# myRolloCtl.net
KiCad netlist of a schematic drawn in EAGLE
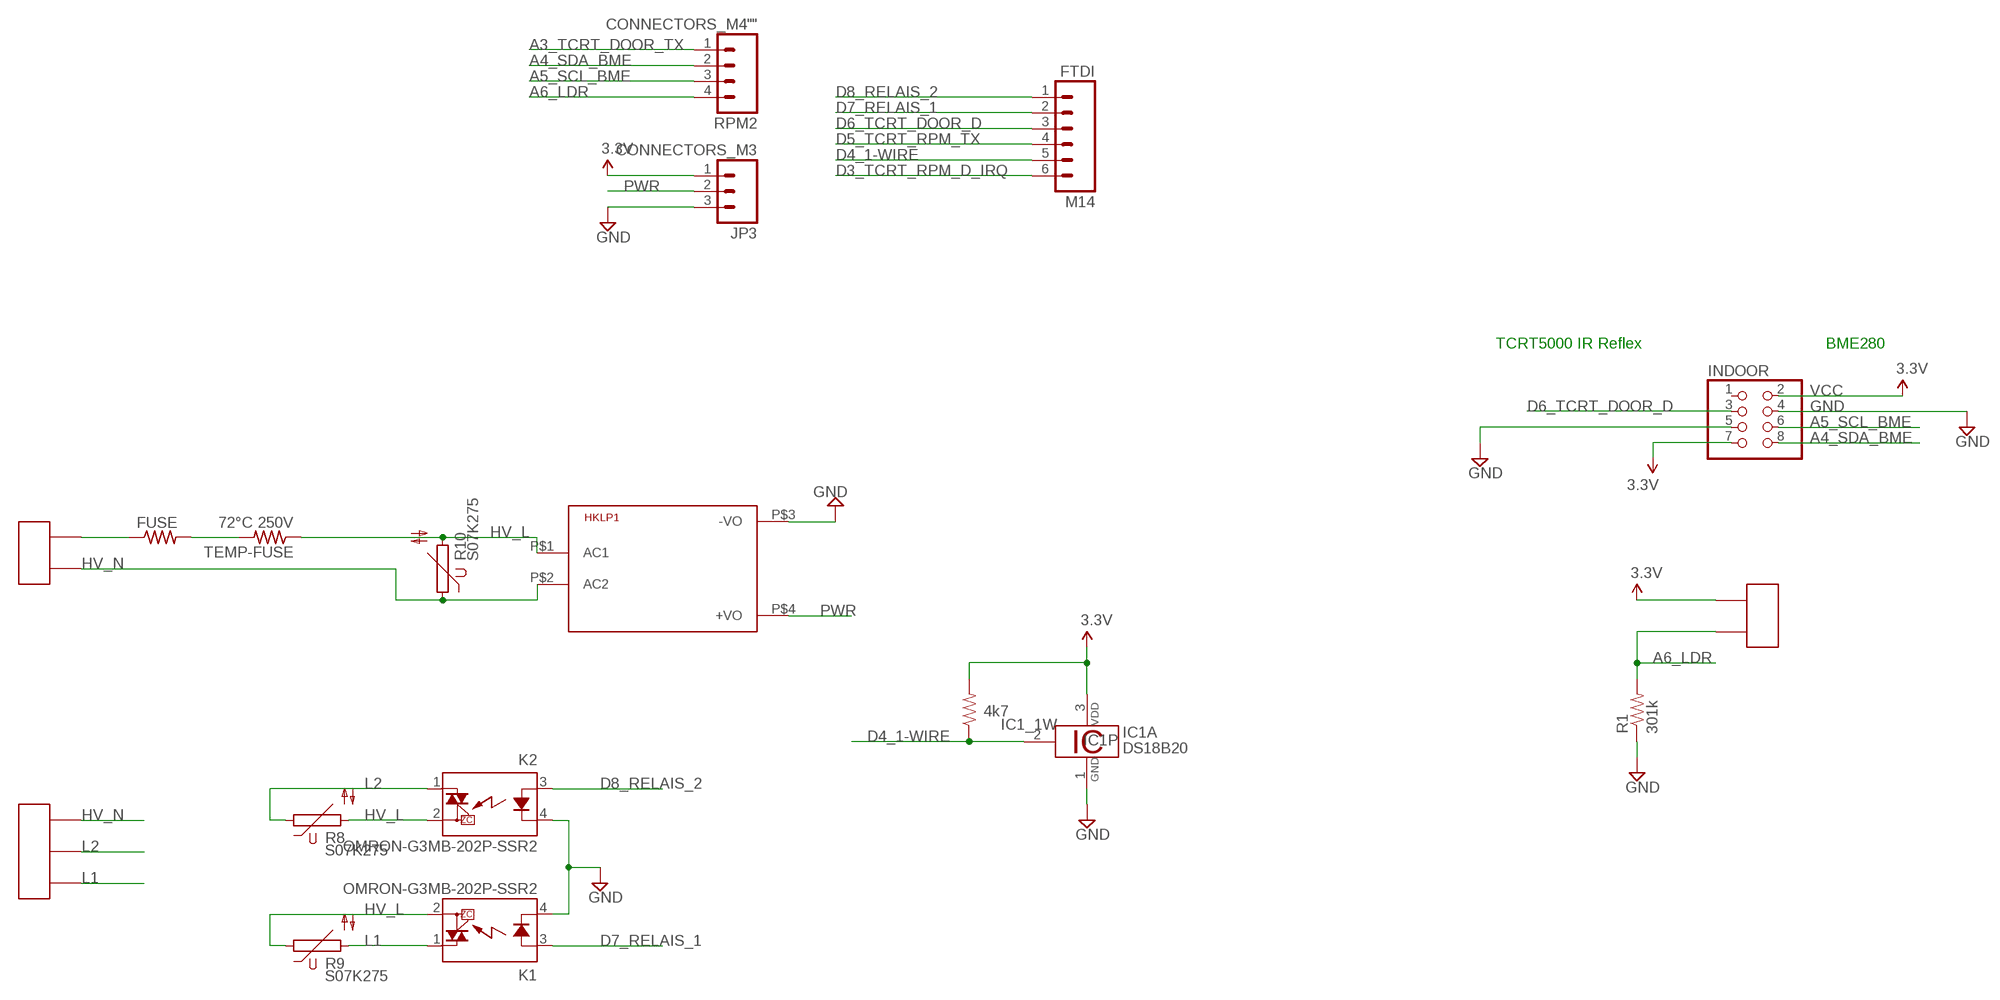
[diagram p0: schematic, sheet 1]

(export (version "E")
  (design (tool "Eeschema 10.0.6"))
  (components
    (comp (ref "FUSE")
      (value "R-US_0613/5V")
      (footprint "eagle-import:P0613V")
      (libsource (lib "eagle-import") (part "R-US_0613/5V"))
    )
    (comp (ref "HKLP1")
      (value "HKLPM01")
      (footprint "eagle-import:HKLPM01")
      (libsource (lib "eagle-import") (part "HKLPM01"))
    )
    (comp (ref "IC1")
      (value "DS18B20")
      (footprint "eagle-import:TO92-")
      (libsource (lib "eagle-import") (part "DS18B20"))
    )
    (comp (ref "INDOOR")
      (value "PINHD-2X4")
      (footprint "eagle-import:2X04")
      (libsource (lib "eagle-import") (part "PINHD-2X4"))
    )
    (comp (ref "JP3")
      (value "CONNECTORS_M3")
      (footprint "eagle-import:CONNECTORS_1X3")
      (libsource (lib "eagle-import") (part "CONNECTORS_M3"))
    )
    (comp (ref "K1")
      (value "OMRON-G3MB-202P-SSR2")
      (footprint "eagle-import:OMRON-G3MB-202P-SSR")
      (fields (field (name "MPN") "S202S02F"))
      (libsource (lib "eagle-import") (part "OMRON-G3MB-202P-SSR2"))
    )
    (comp (ref "K2")
      (value "OMRON-G3MB-202P-SSR2")
      (footprint "eagle-import:OMRON-G3MB-202P-SSR")
      (fields (field (name "MPN") "S202S02F"))
      (libsource (lib "eagle-import") (part "OMRON-G3MB-202P-SSR2"))
    )
    (comp (ref "M14")
      (value "FTDI")
      (footprint "eagle-import:1X06")
      (libsource (lib "eagle-import") (part "M06SIP"))
    )
    (comp (ref "R1")
      (value "301k")
      (footprint "eagle-import:0603-RES")
      (libsource (lib "eagle-import") (part "RESISTOR0603-RES"))
    )
    (comp (ref "R4")
      (value "4k7")
      (footprint "eagle-import:0603-RES")
      (libsource (lib "eagle-import") (part "RESISTOR0603-RES"))
    )
    (comp (ref "R8")
      (value "S07K275")
      (footprint "eagle-import:S07K275")
      (libsource (lib "eagle-import") (part "S07K275"))
    )
    (comp (ref "R9")
      (value "S07K275")
      (footprint "eagle-import:S07K275")
      (libsource (lib "eagle-import") (part "S07K275"))
    )
    (comp (ref "R10")
      (value "S07K275")
      (footprint "eagle-import:S07K275")
      (libsource (lib "eagle-import") (part "S07K275"))
    )
    (comp (ref "RPM2")
      (value "CONNECTORS_M4\"\"")
      (footprint "eagle-import:CONNECTORS_1X4")
      (libsource (lib "eagle-import") (part "CONNECTORS_M4{dblquote}{dblquote}"))
    )
    (comp (ref "TEMP-FUSE")
      (value "72°C 250V")
      (footprint "eagle-import:0207_2V")
      (libsource (lib "eagle-import") (part "R-US_0207/2V"))
    )
    (comp (ref "U$2")
      (value "HDR_2PIN")
      (footprint "eagle-import:1X02_NS")
      (libsource (lib "eagle-import") (part "HDR_2PIN"))
    )
    (comp (ref "U$3")
      (value "HDR_3PIN")
      (footprint "eagle-import:1X03_LUMBERG-KRMC_3,5MM")
      (libsource (lib "eagle-import") (part "HDR_3PIN"))
    )
    (comp (ref "U$6")
      (value "HDR_2PIN1X02_3.5MM")
      (footprint "eagle-import:1X02_LUMBERG-KRMC_3,5MM")
      (libsource (lib "eagle-import") (part "HDR_2PIN1X02_3.5MM"))
    )
  )
  (nets
    (net (code "1") (name "/A3_TCRT_DOOR_TX") (class "Default")
      (node (ref "RPM2") (pin "1") (pinfunction "1_1") (pintype "passive"))
    )
    (net (code "2") (name "/A4_SDA_BME") (class "Default")
      (node (ref "INDOOR") (pin "8") (pinfunction "8_8") (pintype "passive"))
      (node (ref "RPM2") (pin "2") (pinfunction "2_2") (pintype "passive"))
    )
    (net (code "3") (name "/A5_SCL_BME") (class "Default")
      (node (ref "INDOOR") (pin "6") (pinfunction "6_6") (pintype "passive"))
      (node (ref "RPM2") (pin "3") (pinfunction "3_3") (pintype "passive"))
    )
    (net (code "4") (name "/A6_LDR") (class "Default")
      (node (ref "R1") (pin "2") (pinfunction "2_2") (pintype "passive"))
      (node (ref "RPM2") (pin "4") (pinfunction "4_4") (pintype "passive"))
      (node (ref "U$2") (pin "2") (pinfunction "P$2_2") (pintype "bidirectional"))
    )
    (net (code "5") (name "/D3_TCRT_RPM_D_IRQ") (class "Default")
      (node (ref "M14") (pin "6") (pinfunction "6_6") (pintype "passive"))
    )
    (net (code "6") (name "/D4_1-WIRE") (class "Default")
      (node (ref "IC1") (pin "2") (pinfunction "1W_2") (pintype "power_in"))
      (node (ref "M14") (pin "5") (pinfunction "5_5") (pintype "passive"))
      (node (ref "R4") (pin "1") (pinfunction "1_1") (pintype "passive"))
    )
    (net (code "7") (name "/D5_TCRT_RPM_TX") (class "Default")
      (node (ref "M14") (pin "4") (pinfunction "4_4") (pintype "passive"))
    )
    (net (code "8") (name "/D6_TCRT_DOOR_D") (class "Default")
      (node (ref "INDOOR") (pin "3") (pinfunction "3_3") (pintype "passive"))
      (node (ref "M14") (pin "3") (pinfunction "3_3") (pintype "passive"))
    )
    (net (code "9") (name "/D7_RELAIS_1") (class "Default")
      (node (ref "K1") (pin "3") (pinfunction "A_3") (pintype "passive"))
      (node (ref "M14") (pin "2") (pinfunction "2_2") (pintype "passive"))
    )
    (net (code "10") (name "/D8_RELAIS_2") (class "Default")
      (node (ref "K2") (pin "3") (pinfunction "A_3") (pintype "passive"))
      (node (ref "M14") (pin "1") (pinfunction "1_1") (pintype "passive"))
    )
    (net (code "11") (name "/HV_L") (class "Default")
      (node (ref "HKLP1") (pin "P$1") (pinfunction "AC1_P$1") (pintype "bidirectional"))
      (node (ref "K1") (pin "2") (pinfunction "DS2_2") (pintype "passive"))
      (node (ref "K2") (pin "2") (pinfunction "DS2_2") (pintype "passive"))
      (node (ref "R10") (pin "2") (pinfunction "2_2") (pintype "passive"))
      (node (ref "R8") (pin "2") (pinfunction "2_2") (pintype "passive"))
      (node (ref "R9") (pin "1") (pinfunction "1_1") (pintype "passive"))
      (node (ref "TEMP-FUSE") (pin "1") (pinfunction "1_1") (pintype "passive"))
    )
    (net (code "12") (name "/HV_N") (class "Default")
      (node (ref "HKLP1") (pin "P$2") (pinfunction "AC2_P$2") (pintype "bidirectional"))
      (node (ref "R10") (pin "1") (pinfunction "1_1") (pintype "passive"))
      (node (ref "U$3") (pin "3") (pinfunction "P$3_3") (pintype "bidirectional"))
      (node (ref "U$6") (pin "1") (pinfunction "P$1_1") (pintype "bidirectional"))
    )
    (net (code "13") (name "/L1") (class "Default")
      (node (ref "K1") (pin "1") (pinfunction "DS1_1") (pintype "passive"))
      (node (ref "R9") (pin "2") (pinfunction "2_2") (pintype "passive"))
      (node (ref "U$3") (pin "1") (pinfunction "P$1_1") (pintype "bidirectional"))
    )
    (net (code "14") (name "/L2") (class "Default")
      (node (ref "K2") (pin "1") (pinfunction "DS1_1") (pintype "passive"))
      (node (ref "R8") (pin "1") (pinfunction "1_1") (pintype "passive"))
      (node (ref "U$3") (pin "2") (pinfunction "P$2_2") (pintype "bidirectional"))
    )
    (net (code "15") (name "/PWR") (class "Default")
      (node (ref "HKLP1") (pin "P$4") (pinfunction "+VO_P$4") (pintype "bidirectional"))
      (node (ref "JP3") (pin "2") (pinfunction "2_2") (pintype "passive"))
    )
    (net (code "16") (name "3.3V") (class "Default")
      (node (ref "IC1") (pin "3") (pinfunction "VDD_3") (pintype "power_in"))
      (node (ref "INDOOR") (pin "2") (pinfunction "2_2") (pintype "passive"))
      (node (ref "INDOOR") (pin "7") (pinfunction "7_7") (pintype "passive"))
      (node (ref "JP3") (pin "1") (pinfunction "1_1") (pintype "passive"))
      (node (ref "R4") (pin "2") (pinfunction "2_2") (pintype "passive"))
      (node (ref "U$2") (pin "1") (pinfunction "P$1_1") (pintype "bidirectional"))
    )
    (net (code "17") (name "GND") (class "Default")
      (node (ref "HKLP1") (pin "P$3") (pinfunction "-VO_P$3") (pintype "bidirectional"))
      (node (ref "IC1") (pin "1") (pinfunction "GND_1") (pintype "power_in"))
      (node (ref "INDOOR") (pin "4") (pinfunction "4_4") (pintype "passive"))
      (node (ref "INDOOR") (pin "5") (pinfunction "5_5") (pintype "passive"))
      (node (ref "JP3") (pin "3") (pinfunction "3_3") (pintype "passive"))
      (node (ref "K1") (pin "4") (pinfunction "K_4") (pintype "passive"))
      (node (ref "K2") (pin "4") (pinfunction "K_4") (pintype "passive"))
      (node (ref "R1") (pin "1") (pinfunction "1_1") (pintype "passive"))
    )
    (net (code "18") (name "Net-(FUSE-Pad2)") (class "Default")
      (node (ref "FUSE") (pin "2") (pinfunction "2_2") (pintype "passive"))
      (node (ref "TEMP-FUSE") (pin "2") (pinfunction "2_2") (pintype "passive"))
    )
    (net (code "19") (name "Net-(U$6-P$2)") (class "Default")
      (node (ref "FUSE") (pin "1") (pinfunction "1_1") (pintype "passive"))
      (node (ref "U$6") (pin "2") (pinfunction "P$2_2") (pintype "bidirectional"))
    )
    (net (code "20") (name "unconnected-(INDOOR-Pad1)") (class "Default")
      (node (ref "INDOOR") (pin "1") (pinfunction "1_1") (pintype "passive"))
    )
  )
)
